# schematics.net
KiCad netlist of a schematic drawn in EasyEDA
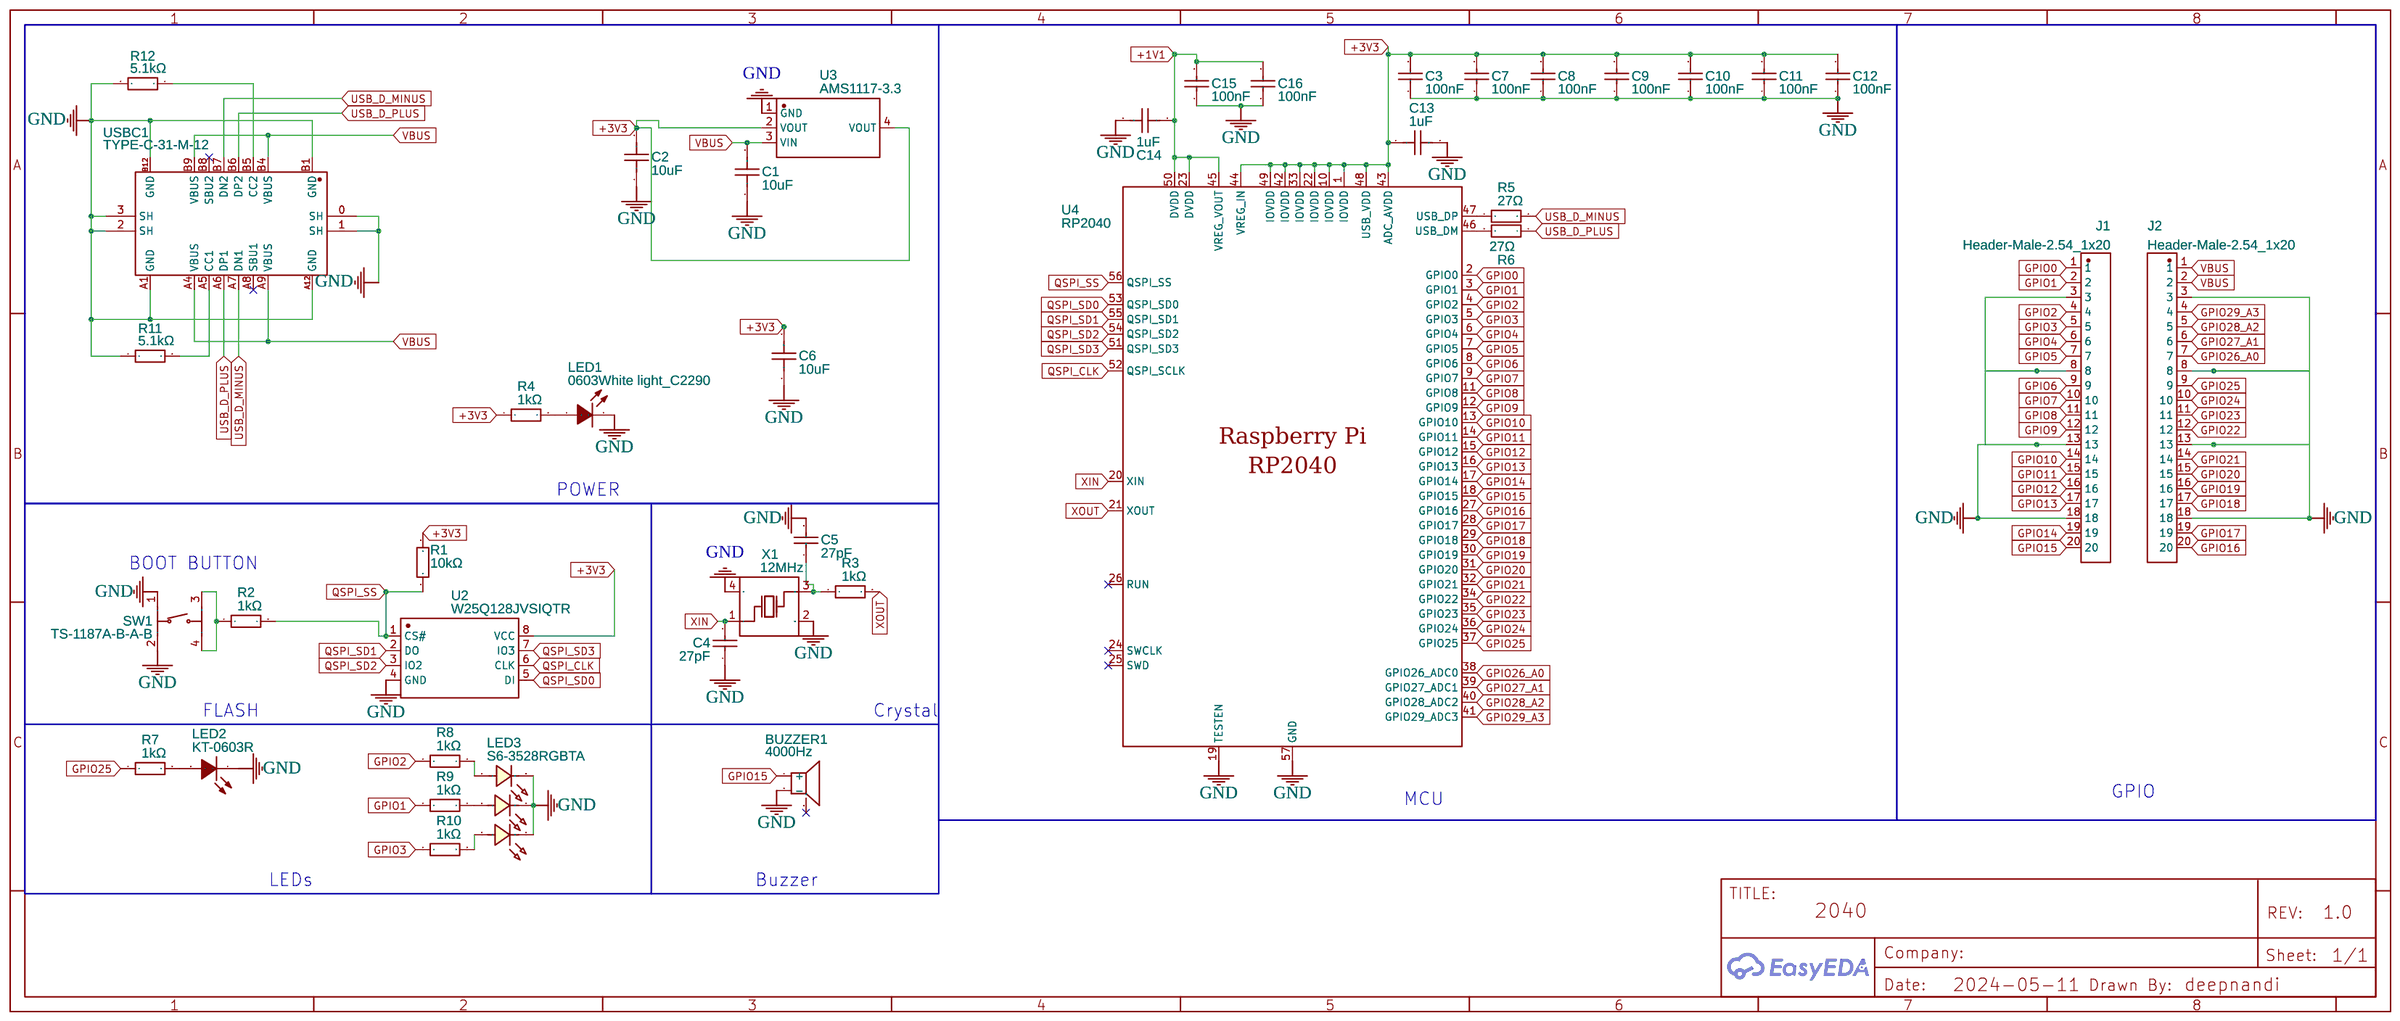
[diagram p0: schematic sheet]

(export (version "E")
  (design (tool "Eeschema 10.0.6"))
  (components
    (comp (ref "BUZZER1")
      (value "4000Hz")
      (fields (field (name "Manufacturer Part") "MLT-5020") (field (name "Manufacturer") "华能"))
      (libsource (lib "") (part "MLT-5020"))
    )
    (comp (ref "C1")
      (value "10uF")
      (fields
        (field (name "Manufacturer Part") "CL10A106KP8NNNC")
        (field (name "Manufacturer") "SAMSUNG(三星)")
      )
      (libsource (lib "") (part "CL10A106KP8NNNC"))
    )
    (comp (ref "C2")
      (value "10uF")
      (fields
        (field (name "Manufacturer Part") "CL10A106KP8NNNC")
        (field (name "Manufacturer") "SAMSUNG(三星)")
      )
      (libsource (lib "") (part "CL10A106KP8NNNC"))
    )
    (comp (ref "C3")
      (value "100nF")
      (fields
        (field (name "Manufacturer Part") "CL05B104KO5NNNC")
        (field (name "Manufacturer") "SAMSUNG(三星)")
      )
      (libsource (lib "") (part "CL05B104KO5NNNC"))
    )
    (comp (ref "C4")
      (value "27pF")
      (fields
        (field (name "Manufacturer Part") "CC0603JRNPO9BN270")
        (field (name "Manufacturer") "YAGEO(国巨)")
      )
      (libsource (lib "") (part "CC0603JRNPO9BN270_1"))
    )
    (comp (ref "C5")
      (value "27pF")
      (fields
        (field (name "Manufacturer Part") "CC0603JRNPO9BN270")
        (field (name "Manufacturer") "YAGEO(国巨)")
      )
      (libsource (lib "") (part "CC0603JRNPO9BN270"))
    )
    (comp (ref "C6")
      (value "10uF")
      (fields
        (field (name "Manufacturer Part") "CL10A106KP8NNNC")
        (field (name "Manufacturer") "SAMSUNG(三星)")
      )
      (libsource (lib "") (part "CL10A106KP8NNNC"))
    )
    (comp (ref "C7")
      (value "100nF")
      (fields
        (field (name "Manufacturer Part") "CL05B104KO5NNNC")
        (field (name "Manufacturer") "SAMSUNG(三星)")
      )
      (libsource (lib "") (part "CL05B104KO5NNNC"))
    )
    (comp (ref "C8")
      (value "100nF")
      (fields
        (field (name "Manufacturer Part") "CL05B104KO5NNNC")
        (field (name "Manufacturer") "SAMSUNG(三星)")
      )
      (libsource (lib "") (part "CL05B104KO5NNNC"))
    )
    (comp (ref "C9")
      (value "100nF")
      (fields
        (field (name "Manufacturer Part") "CL05B104KO5NNNC")
        (field (name "Manufacturer") "SAMSUNG(三星)")
      )
      (libsource (lib "") (part "CL05B104KO5NNNC"))
    )
    (comp (ref "C10")
      (value "100nF")
      (fields
        (field (name "Manufacturer Part") "CL05B104KO5NNNC")
        (field (name "Manufacturer") "SAMSUNG(三星)")
      )
      (libsource (lib "") (part "CL05B104KO5NNNC"))
    )
    (comp (ref "C11")
      (value "100nF")
      (fields
        (field (name "Manufacturer Part") "CL05B104KO5NNNC")
        (field (name "Manufacturer") "SAMSUNG(三星)")
      )
      (libsource (lib "") (part "CL05B104KO5NNNC"))
    )
    (comp (ref "C12")
      (value "100nF")
      (fields
        (field (name "Manufacturer Part") "CL05B104KO5NNNC")
        (field (name "Manufacturer") "SAMSUNG(三星)")
      )
      (libsource (lib "") (part "CL05B104KO5NNNC"))
    )
    (comp (ref "C13")
      (value "1uF")
      (fields
        (field (name "Manufacturer Part") "CL05A105KA5NQNC")
        (field (name "Manufacturer") "SAMSUNG(三星)")
      )
      (libsource (lib "") (part "CL05A105KA5NQNC"))
    )
    (comp (ref "C14")
      (value "1uF")
      (fields
        (field (name "Manufacturer Part") "CL05A105KA5NQNC")
        (field (name "Manufacturer") "SAMSUNG(三星)")
      )
      (libsource (lib "") (part "CL05A105KA5NQNC_1"))
    )
    (comp (ref "C15")
      (value "100nF")
      (fields
        (field (name "Manufacturer Part") "CL05B104KO5NNNC")
        (field (name "Manufacturer") "SAMSUNG(三星)")
      )
      (libsource (lib "") (part "CL05B104KO5NNNC"))
    )
    (comp (ref "C16")
      (value "100nF")
      (fields
        (field (name "Manufacturer Part") "CL05B104KO5NNNC")
        (field (name "Manufacturer") "SAMSUNG(三星)")
      )
      (libsource (lib "") (part "CL05B104KO5NNNC"))
    )
    (comp (ref "J1")
      (value "Header-Male-2.54_1x20")
      (fields (field (name "Manufacturer Part") "2.54-1*20P直针") (field (name "Manufacturer") "BOOMELE(博穆精密)"))
      (libsource (lib "") (part "Header-Male-2.54_1x20"))
    )
    (comp (ref "J2")
      (value "Header-Male-2.54_1x20")
      (fields (field (name "Manufacturer Part") "2.54-1*20P直针") (field (name "Manufacturer") "BOOMELE(博穆精密)"))
      (libsource (lib "") (part "Header-Male-2.54_1x20_1"))
    )
    (comp (ref "LED1")
      (value "0603White light_C2290")
      (fields (field (name "Manufacturer Part") "KT-0603白灯") (field (name "Manufacturer") "KENTO"))
      (libsource (lib "") (part "0603White light_C2290"))
    )
    (comp (ref "LED2")
      (value "KT-0603R")
      (fields (field (name "Manufacturer") "KENTO"))
      (libsource (lib "") (part "KT-0603R"))
    )
    (comp (ref "LED3")
      (value "S6-3528RGBTA")
      (fields (field (name "Manufacturer") "TUOZHAN(拓展光电)"))
      (libsource (lib "") (part "S6-3528RGBTA"))
    )
    (comp (ref "R1")
      (value "10kΩ")
      (fields
        (field (name "Manufacturer Part") "0402WGF1002TCE")
        (field (name "Manufacturer") "UNI-ROYAL(厚声)")
      )
      (libsource (lib "") (part "0402WGF1002TCE"))
    )
    (comp (ref "R2")
      (value "1kΩ")
      (fields
        (field (name "Manufacturer Part") "0402WGF1001TCE")
        (field (name "Manufacturer") "UNI-ROYAL(厚声)")
      )
      (libsource (lib "") (part "0402WGF1001TCE"))
    )
    (comp (ref "R3")
      (value "1kΩ")
      (fields
        (field (name "Manufacturer Part") "0402WGF1001TCE")
        (field (name "Manufacturer") "UNI-ROYAL(厚声)")
      )
      (libsource (lib "") (part "0402WGF1001TCE"))
    )
    (comp (ref "R4")
      (value "1kΩ")
      (fields
        (field (name "Manufacturer Part") "0402WGF1001TCE")
        (field (name "Manufacturer") "UNI-ROYAL(厚声)")
      )
      (libsource (lib "") (part "0402WGF1001TCE"))
    )
    (comp (ref "R5")
      (value "27Ω")
      (fields
        (field (name "Manufacturer Part") "0805W8F270JT5E")
        (field (name "Manufacturer") "UNI-ROYAL(厚声)")
      )
      (libsource (lib "") (part "0805W8F270JT5E_1"))
    )
    (comp (ref "R6")
      (value "27Ω")
      (fields
        (field (name "Manufacturer Part") "0805W8F270JT5E")
        (field (name "Manufacturer") "UNI-ROYAL(厚声)")
      )
      (libsource (lib "") (part "0805W8F270JT5E"))
    )
    (comp (ref "R7")
      (value "1kΩ")
      (fields
        (field (name "Manufacturer Part") "0402WGF1001TCE")
        (field (name "Manufacturer") "UNI-ROYAL(厚声)")
      )
      (libsource (lib "") (part "0402WGF1001TCE"))
    )
    (comp (ref "R8")
      (value "1kΩ")
      (fields
        (field (name "Manufacturer Part") "0402WGF1001TCE")
        (field (name "Manufacturer") "UNI-ROYAL(厚声)")
      )
      (libsource (lib "") (part "0402WGF1001TCE"))
    )
    (comp (ref "R9")
      (value "1kΩ")
      (fields
        (field (name "Manufacturer Part") "0402WGF1001TCE")
        (field (name "Manufacturer") "UNI-ROYAL(厚声)")
      )
      (libsource (lib "") (part "0402WGF1001TCE"))
    )
    (comp (ref "R10")
      (value "1kΩ")
      (fields
        (field (name "Manufacturer Part") "0402WGF1001TCE")
        (field (name "Manufacturer") "UNI-ROYAL(厚声)")
      )
      (libsource (lib "") (part "0402WGF1001TCE"))
    )
    (comp (ref "R11")
      (value "5.1kΩ")
      (fields (field (name "Manufacturer Part") "RTT02512JTH") (field (name "Manufacturer") "RALEC(旺诠)"))
      (libsource (lib "") (part "RTT02512JTH"))
    )
    (comp (ref "R12")
      (value "5.1kΩ")
      (fields (field (name "Manufacturer Part") "RTT02512JTH") (field (name "Manufacturer") "RALEC(旺诠)"))
      (libsource (lib "") (part "RTT02512JTH_1"))
    )
    (comp (ref "SW1")
      (value "TS-1187A-B-A-B")
      (fields (field (name "Manufacturer") "XKB Connectivity(中国星坤)"))
      (libsource (lib "") (part "TS-1187A-B-A-B"))
    )
    (comp (ref "U2")
      (value "W25Q128JVSIQTR")
      (fields (field (name "Manufacturer Part") "W25Q128JVSIQ") (field (name "Manufacturer") "WINBOND(华邦)"))
      (libsource (lib "") (part "W25Q128JVSIQTR"))
    )
    (comp (ref "U3")
      (value "AMS1117-3.3")
      (fields (field (name "Manufacturer") "AMS"))
      (libsource (lib "") (part "AMS1117-3.3"))
    )
    (comp (ref "U4")
      (value "RP2040")
      (fields (field (name "Manufacturer") "Raspberry Pi(树莓派)"))
      (libsource (lib "") (part "RP2040"))
    )
    (comp (ref "USBC1")
      (value "TYPE-C-31-M-12")
      (fields (field (name "Manufacturer") "韩国韩荣"))
      (libsource (lib "") (part "TYPE-C-31-M-12"))
    )
    (comp (ref "X1")
      (value "12MHz")
      (fields (field (name "Manufacturer Part") "X322512MSB4SI") (field (name "Manufacturer") "YXC(扬兴晶振)"))
      (libsource (lib "") (part "X322512MSB4SI"))
    )
  )
  (nets
    (net (code "1") (name "+1V1") (class "Default")
      (node (ref "C14") (pin "2") (pinfunction "2_2") (pintype "unspecified"))
      (node (ref "C15") (pin "2") (pinfunction "2_2") (pintype "input"))
      (node (ref "C16") (pin "2") (pinfunction "2_2") (pintype "input"))
      (node (ref "U4") (pin "23") (pinfunction "DVDD_23") (pintype "bidirectional"))
      (node (ref "U4") (pin "45") (pinfunction "VREG_VOUT_45") (pintype "bidirectional"))
      (node (ref "U4") (pin "50") (pinfunction "DVDD_50") (pintype "bidirectional"))
    )
    (net (code "2") (name "+3V3") (class "Default")
      (node (ref "C10") (pin "2") (pinfunction "2_2") (pintype "input"))
      (node (ref "C11") (pin "2") (pinfunction "2_2") (pintype "input"))
      (node (ref "C12") (pin "2") (pinfunction "2_2") (pintype "input"))
      (node (ref "C13") (pin "1") (pinfunction "1_1") (pintype "unspecified"))
      (node (ref "C2") (pin "2") (pinfunction "2_2") (pintype "unspecified"))
      (node (ref "C3") (pin "2") (pinfunction "2_2") (pintype "input"))
      (node (ref "C6") (pin "2") (pinfunction "2_2") (pintype "unspecified"))
      (node (ref "C7") (pin "2") (pinfunction "2_2") (pintype "input"))
      (node (ref "C8") (pin "2") (pinfunction "2_2") (pintype "input"))
      (node (ref "C9") (pin "2") (pinfunction "2_2") (pintype "input"))
      (node (ref "R1") (pin "2") (pinfunction "2_2") (pintype "input"))
      (node (ref "R4") (pin "1") (pinfunction "1_1") (pintype "input"))
      (node (ref "U2") (pin "8") (pinfunction "VCC_8") (pintype "unspecified"))
      (node (ref "U3") (pin "2") (pinfunction "VOUT_2") (pintype "unspecified"))
      (node (ref "U3") (pin "4") (pinfunction "VOUT_4") (pintype "unspecified"))
      (node (ref "U4") (pin "1") (pinfunction "IOVDD_1") (pintype "bidirectional"))
      (node (ref "U4") (pin "10") (pinfunction "IOVDD_10") (pintype "bidirectional"))
      (node (ref "U4") (pin "22") (pinfunction "IOVDD_22") (pintype "bidirectional"))
      (node (ref "U4") (pin "33") (pinfunction "IOVDD_33") (pintype "bidirectional"))
      (node (ref "U4") (pin "42") (pinfunction "IOVDD_42") (pintype "bidirectional"))
      (node (ref "U4") (pin "43") (pinfunction "ADC_AVDD_43") (pintype "bidirectional"))
      (node (ref "U4") (pin "44") (pinfunction "VREG_IN_44") (pintype "bidirectional"))
      (node (ref "U4") (pin "48") (pinfunction "USB_VDD_48") (pintype "bidirectional"))
      (node (ref "U4") (pin "49") (pinfunction "IOVDD_49") (pintype "bidirectional"))
    )
    (net (code "3") (name "GND") (class "Default")
      (node (ref "BUZZER1") (pin "2") (pinfunction "-_2") (pintype "unspecified"))
      (node (ref "C1") (pin "1") (pinfunction "1_1") (pintype "unspecified"))
      (node (ref "C10") (pin "1") (pinfunction "1_1") (pintype "input"))
      (node (ref "C11") (pin "1") (pinfunction "1_1") (pintype "input"))
      (node (ref "C12") (pin "1") (pinfunction "1_1") (pintype "input"))
      (node (ref "C13") (pin "2") (pinfunction "2_2") (pintype "unspecified"))
      (node (ref "C14") (pin "1") (pinfunction "1_1") (pintype "unspecified"))
      (node (ref "C15") (pin "1") (pinfunction "1_1") (pintype "input"))
      (node (ref "C16") (pin "1") (pinfunction "1_1") (pintype "input"))
      (node (ref "C2") (pin "1") (pinfunction "1_1") (pintype "unspecified"))
      (node (ref "C3") (pin "1") (pinfunction "1_1") (pintype "input"))
      (node (ref "C4") (pin "1") (pinfunction "1_1") (pintype "input"))
      (node (ref "C5") (pin "2") (pinfunction "2_2") (pintype "input"))
      (node (ref "C6") (pin "1") (pinfunction "1_1") (pintype "unspecified"))
      (node (ref "C7") (pin "1") (pinfunction "1_1") (pintype "input"))
      (node (ref "C8") (pin "1") (pinfunction "1_1") (pintype "input"))
      (node (ref "C9") (pin "1") (pinfunction "1_1") (pintype "input"))
      (node (ref "J1") (pin "13") (pinfunction "13_13") (pintype "unspecified"))
      (node (ref "J1") (pin "18") (pinfunction "18_18") (pintype "unspecified"))
      (node (ref "J1") (pin "3") (pinfunction "3_3") (pintype "unspecified"))
      (node (ref "J1") (pin "8") (pinfunction "8_8") (pintype "unspecified"))
      (node (ref "J2") (pin "13") (pinfunction "13_13") (pintype "unspecified"))
      (node (ref "J2") (pin "18") (pinfunction "18_18") (pintype "unspecified"))
      (node (ref "J2") (pin "3") (pinfunction "3_3") (pintype "unspecified"))
      (node (ref "J2") (pin "8") (pinfunction "8_8") (pintype "unspecified"))
      (node (ref "LED1") (pin "2") (pinfunction "K_2") (pintype "unspecified"))
      (node (ref "LED2") (pin "1") (pinfunction "K_1") (pintype "unspecified"))
      (node (ref "LED3") (pin "1") (pinfunction "1_1") (pintype "unspecified"))
      (node (ref "LED3") (pin "2") (pinfunction "2_2") (pintype "unspecified"))
      (node (ref "LED3") (pin "3") (pinfunction "3_3") (pintype "unspecified"))
      (node (ref "R11") (pin "1") (pinfunction "1_1") (pintype "input"))
      (node (ref "R12") (pin "2") (pinfunction "2_2") (pintype "input"))
      (node (ref "SW1") (pin "1") (pinfunction "A_1") (pintype "unspecified"))
      (node (ref "SW1") (pin "2") (pinfunction "B_2") (pintype "unspecified"))
      (node (ref "U2") (pin "4") (pinfunction "GND_4") (pintype "unspecified"))
      (node (ref "U3") (pin "1") (pinfunction "GND_1") (pintype "unspecified"))
      (node (ref "U4") (pin "19") (pinfunction "TESTEN_19") (pintype "unspecified"))
      (node (ref "U4") (pin "57") (pinfunction "GND_57") (pintype "bidirectional"))
      (node (ref "USBC1") (pin "0") (pinfunction "SH_0") (pintype "unspecified"))
      (node (ref "USBC1") (pin "1") (pinfunction "SH_1") (pintype "unspecified"))
      (node (ref "USBC1") (pin "2") (pinfunction "SH_2") (pintype "unspecified"))
      (node (ref "USBC1") (pin "3") (pinfunction "SH_3") (pintype "unspecified"))
      (node (ref "USBC1") (pin "A1") (pinfunction "GND_A1") (pintype "unspecified"))
      (node (ref "USBC1") (pin "A12") (pinfunction "GND_A12") (pintype "unspecified"))
      (node (ref "USBC1") (pin "B1") (pinfunction "GND_B1") (pintype "unspecified"))
      (node (ref "USBC1") (pin "B12") (pinfunction "GND_B12") (pintype "unspecified"))
      (node (ref "X1") (pin "2") (pinfunction "GND_2") (pintype "unspecified"))
      (node (ref "X1") (pin "4") (pinfunction "GND_4") (pintype "unspecified"))
    )
    (net (code "4") (name "GPIO0") (class "Default")
      (node (ref "J1") (pin "1") (pinfunction "1_1") (pintype "unspecified"))
      (node (ref "U4") (pin "2") (pinfunction "GPIO0_2") (pintype "bidirectional"))
    )
    (net (code "5") (name "GPIO1") (class "Default")
      (node (ref "J1") (pin "2") (pinfunction "2_2") (pintype "unspecified"))
      (node (ref "R9") (pin "1") (pinfunction "1_1") (pintype "input"))
      (node (ref "U4") (pin "3") (pinfunction "GPIO1_3") (pintype "bidirectional"))
    )
    (net (code "6") (name "GPIO2") (class "Default")
      (node (ref "J1") (pin "4") (pinfunction "4_4") (pintype "unspecified"))
      (node (ref "R8") (pin "1") (pinfunction "1_1") (pintype "input"))
      (node (ref "U4") (pin "4") (pinfunction "GPIO2_4") (pintype "bidirectional"))
    )
    (net (code "7") (name "GPIO3") (class "Default")
      (node (ref "J1") (pin "5") (pinfunction "5_5") (pintype "unspecified"))
      (node (ref "R10") (pin "1") (pinfunction "1_1") (pintype "input"))
      (node (ref "U4") (pin "5") (pinfunction "GPIO3_5") (pintype "bidirectional"))
    )
    (net (code "8") (name "GPIO4") (class "Default")
      (node (ref "J1") (pin "6") (pinfunction "6_6") (pintype "unspecified"))
      (node (ref "U4") (pin "6") (pinfunction "GPIO4_6") (pintype "bidirectional"))
    )
    (net (code "9") (name "GPIO5") (class "Default")
      (node (ref "J1") (pin "7") (pinfunction "7_7") (pintype "unspecified"))
      (node (ref "U4") (pin "7") (pinfunction "GPIO5_7") (pintype "bidirectional"))
    )
    (net (code "10") (name "GPIO6") (class "Default")
      (node (ref "J1") (pin "9") (pinfunction "9_9") (pintype "unspecified"))
      (node (ref "U4") (pin "8") (pinfunction "GPIO6_8") (pintype "bidirectional"))
    )
    (net (code "11") (name "GPIO7") (class "Default")
      (node (ref "J1") (pin "10") (pinfunction "10_10") (pintype "unspecified"))
      (node (ref "U4") (pin "9") (pinfunction "GPIO7_9") (pintype "bidirectional"))
    )
    (net (code "12") (name "GPIO8") (class "Default")
      (node (ref "J1") (pin "11") (pinfunction "11_11") (pintype "unspecified"))
      (node (ref "U4") (pin "11") (pinfunction "GPIO8_11") (pintype "bidirectional"))
    )
    (net (code "13") (name "GPIO9") (class "Default")
      (node (ref "J1") (pin "12") (pinfunction "12_12") (pintype "unspecified"))
      (node (ref "U4") (pin "12") (pinfunction "GPIO9_12") (pintype "bidirectional"))
    )
    (net (code "14") (name "GPIO10") (class "Default")
      (node (ref "J1") (pin "14") (pinfunction "14_14") (pintype "unspecified"))
      (node (ref "U4") (pin "13") (pinfunction "GPIO10_13") (pintype "bidirectional"))
    )
    (net (code "15") (name "GPIO11") (class "Default")
      (node (ref "J1") (pin "15") (pinfunction "15_15") (pintype "unspecified"))
      (node (ref "U4") (pin "14") (pinfunction "GPIO11_14") (pintype "bidirectional"))
    )
    (net (code "16") (name "GPIO12") (class "Default")
      (node (ref "J1") (pin "16") (pinfunction "16_16") (pintype "unspecified"))
      (node (ref "U4") (pin "15") (pinfunction "GPIO12_15") (pintype "bidirectional"))
    )
    (net (code "17") (name "GPIO13") (class "Default")
      (node (ref "J1") (pin "17") (pinfunction "17_17") (pintype "unspecified"))
      (node (ref "U4") (pin "16") (pinfunction "GPIO13_16") (pintype "bidirectional"))
    )
    (net (code "18") (name "GPIO14") (class "Default")
      (node (ref "J1") (pin "19") (pinfunction "19_19") (pintype "unspecified"))
      (node (ref "U4") (pin "17") (pinfunction "GPIO14_17") (pintype "bidirectional"))
    )
    (net (code "19") (name "GPIO15") (class "Default")
      (node (ref "BUZZER1") (pin "1") (pinfunction "+_1") (pintype "unspecified"))
      (node (ref "J1") (pin "20") (pinfunction "20_20") (pintype "unspecified"))
      (node (ref "U4") (pin "18") (pinfunction "GPIO15_18") (pintype "bidirectional"))
    )
    (net (code "20") (name "GPIO16") (class "Default")
      (node (ref "J2") (pin "20") (pinfunction "20_20") (pintype "unspecified"))
      (node (ref "U4") (pin "27") (pinfunction "GPIO16_27") (pintype "bidirectional"))
    )
    (net (code "21") (name "GPIO17") (class "Default")
      (node (ref "J2") (pin "19") (pinfunction "19_19") (pintype "unspecified"))
      (node (ref "U4") (pin "28") (pinfunction "GPIO17_28") (pintype "bidirectional"))
    )
    (net (code "22") (name "GPIO18") (class "Default")
      (node (ref "J2") (pin "17") (pinfunction "17_17") (pintype "unspecified"))
      (node (ref "U4") (pin "29") (pinfunction "GPIO18_29") (pintype "bidirectional"))
    )
    (net (code "23") (name "GPIO19") (class "Default")
      (node (ref "J2") (pin "16") (pinfunction "16_16") (pintype "unspecified"))
      (node (ref "U4") (pin "30") (pinfunction "GPIO19_30") (pintype "bidirectional"))
    )
    (net (code "24") (name "GPIO20") (class "Default")
      (node (ref "J2") (pin "15") (pinfunction "15_15") (pintype "unspecified"))
      (node (ref "U4") (pin "31") (pinfunction "GPIO20_31") (pintype "bidirectional"))
    )
    (net (code "25") (name "GPIO21") (class "Default")
      (node (ref "J2") (pin "14") (pinfunction "14_14") (pintype "unspecified"))
      (node (ref "U4") (pin "32") (pinfunction "GPIO21_32") (pintype "bidirectional"))
    )
    (net (code "26") (name "GPIO22") (class "Default")
      (node (ref "J2") (pin "12") (pinfunction "12_12") (pintype "unspecified"))
      (node (ref "U4") (pin "34") (pinfunction "GPIO22_34") (pintype "bidirectional"))
    )
    (net (code "27") (name "GPIO23") (class "Default")
      (node (ref "J2") (pin "11") (pinfunction "11_11") (pintype "unspecified"))
      (node (ref "U4") (pin "35") (pinfunction "GPIO23_35") (pintype "bidirectional"))
    )
    (net (code "28") (name "GPIO24") (class "Default")
      (node (ref "J2") (pin "10") (pinfunction "10_10") (pintype "unspecified"))
      (node (ref "U4") (pin "36") (pinfunction "GPIO24_36") (pintype "bidirectional"))
    )
    (net (code "29") (name "GPIO25") (class "Default")
      (node (ref "J2") (pin "9") (pinfunction "9_9") (pintype "unspecified"))
      (node (ref "R7") (pin "1") (pinfunction "1_1") (pintype "input"))
      (node (ref "U4") (pin "37") (pinfunction "GPIO25_37") (pintype "bidirectional"))
    )
    (net (code "30") (name "GPIO26_A0") (class "Default")
      (node (ref "J2") (pin "7") (pinfunction "7_7") (pintype "unspecified"))
      (node (ref "U4") (pin "38") (pinfunction "GPIO26_ADC0_38") (pintype "bidirectional"))
    )
    (net (code "31") (name "GPIO27_A1") (class "Default")
      (node (ref "J2") (pin "6") (pinfunction "6_6") (pintype "unspecified"))
      (node (ref "U4") (pin "39") (pinfunction "GPIO27_ADC1_39") (pintype "bidirectional"))
    )
    (net (code "32") (name "GPIO28_A2") (class "Default")
      (node (ref "J2") (pin "5") (pinfunction "5_5") (pintype "unspecified"))
      (node (ref "U4") (pin "40") (pinfunction "GPIO28_ADC2_40") (pintype "bidirectional"))
    )
    (net (code "33") (name "GPIO29_A3") (class "Default")
      (node (ref "J2") (pin "4") (pinfunction "4_4") (pintype "unspecified"))
      (node (ref "U4") (pin "41") (pinfunction "GPIO29_ADC3_41") (pintype "bidirectional"))
    )
    (net (code "34") (name "Net-(LED1-A)") (class "Default")
      (node (ref "LED1") (pin "1") (pinfunction "A_1") (pintype "unspecified"))
      (node (ref "R4") (pin "2") (pinfunction "2_2") (pintype "input"))
    )
    (net (code "35") (name "Net-(LED2-A)") (class "Default")
      (node (ref "LED2") (pin "2") (pinfunction "A_2") (pintype "unspecified"))
      (node (ref "R7") (pin "2") (pinfunction "2_2") (pintype "input"))
    )
    (net (code "36") (name "Net-(LED3-Pad4)") (class "Default")
      (node (ref "LED3") (pin "4") (pinfunction "4_4") (pintype "unspecified"))
      (node (ref "R8") (pin "2") (pinfunction "2_2") (pintype "input"))
    )
    (net (code "37") (name "Net-(LED3-Pad5)") (class "Default")
      (node (ref "LED3") (pin "5") (pinfunction "5_5") (pintype "unspecified"))
      (node (ref "R9") (pin "2") (pinfunction "2_2") (pintype "input"))
    )
    (net (code "38") (name "Net-(LED3-Pad6)") (class "Default")
      (node (ref "LED3") (pin "6") (pinfunction "6_6") (pintype "unspecified"))
      (node (ref "R10") (pin "2") (pinfunction "2_2") (pintype "input"))
    )
    (net (code "39") (name "Net-(SW1-C)") (class "Default")
      (node (ref "R2") (pin "1") (pinfunction "1_1") (pintype "input"))
      (node (ref "SW1") (pin "3") (pinfunction "C_3") (pintype "unspecified"))
      (node (ref "SW1") (pin "4") (pinfunction "D_4") (pintype "unspecified"))
    )
    (net (code "40") (name "Net-(U4-USB_DM)") (class "Default")
      (node (ref "R6") (pin "2") (pinfunction "2_2") (pintype "input"))
      (node (ref "U4") (pin "46") (pinfunction "USB_DM_46") (pintype "bidirectional"))
    )
    (net (code "41") (name "Net-(U4-USB_DP)") (class "Default")
      (node (ref "R5") (pin "1") (pinfunction "1_1") (pintype "input"))
      (node (ref "U4") (pin "47") (pinfunction "USB_DP_47") (pintype "bidirectional"))
    )
    (net (code "42") (name "Net-(USBC1-CC1)") (class "Default")
      (node (ref "R11") (pin "2") (pinfunction "2_2") (pintype "input"))
      (node (ref "USBC1") (pin "A5") (pinfunction "CC1_A5") (pintype "unspecified"))
    )
    (net (code "43") (name "Net-(USBC1-CC2)") (class "Default")
      (node (ref "R12") (pin "1") (pinfunction "1_1") (pintype "input"))
      (node (ref "USBC1") (pin "B5") (pinfunction "CC2_B5") (pintype "unspecified"))
    )
    (net (code "44") (name "Net-(X1-OSC2)") (class "Default")
      (node (ref "C5") (pin "1") (pinfunction "1_1") (pintype "input"))
      (node (ref "R3") (pin "1") (pinfunction "1_1") (pintype "input"))
      (node (ref "X1") (pin "3") (pinfunction "OSC2_3") (pintype "unspecified"))
    )
    (net (code "45") (name "QSPI_CLK") (class "Default")
      (node (ref "U2") (pin "6") (pinfunction "CLK_6") (pintype "unspecified"))
      (node (ref "U4") (pin "52") (pinfunction "QSPI_SCLK_52") (pintype "output"))
    )
    (net (code "46") (name "QSPI_SD0") (class "Default")
      (node (ref "U2") (pin "5") (pinfunction "DI_5") (pintype "unspecified"))
      (node (ref "U4") (pin "53") (pinfunction "QSPI_SD0_53") (pintype "bidirectional"))
    )
    (net (code "47") (name "QSPI_SD1") (class "Default")
      (node (ref "U2") (pin "2") (pinfunction "DO_2") (pintype "unspecified"))
      (node (ref "U4") (pin "55") (pinfunction "QSPI_SD1_55") (pintype "bidirectional"))
    )
    (net (code "48") (name "QSPI_SD2") (class "Default")
      (node (ref "U2") (pin "3") (pinfunction "IO2_3") (pintype "unspecified"))
      (node (ref "U4") (pin "54") (pinfunction "QSPI_SD2_54") (pintype "bidirectional"))
    )
    (net (code "49") (name "QSPI_SD3") (class "Default")
      (node (ref "U2") (pin "7") (pinfunction "IO3_7") (pintype "unspecified"))
      (node (ref "U4") (pin "51") (pinfunction "QSPI_SD3_51") (pintype "bidirectional"))
    )
    (net (code "50") (name "QSPI_SS") (class "Default")
      (node (ref "R1") (pin "1") (pinfunction "1_1") (pintype "input"))
      (node (ref "R2") (pin "2") (pinfunction "2_2") (pintype "input"))
      (node (ref "U2") (pin "1") (pinfunction "CS#_1") (pintype "unspecified"))
      (node (ref "U4") (pin "56") (pinfunction "QSPI_SS_56") (pintype "bidirectional"))
    )
    (net (code "51") (name "USB_D_MINUS") (class "Default")
      (node (ref "R5") (pin "2") (pinfunction "2_2") (pintype "input"))
      (node (ref "USBC1") (pin "A7") (pinfunction "DN1_A7") (pintype "unspecified"))
      (node (ref "USBC1") (pin "B7") (pinfunction "DN2_B7") (pintype "unspecified"))
    )
    (net (code "52") (name "USB_D_PLUS") (class "Default")
      (node (ref "R6") (pin "1") (pinfunction "1_1") (pintype "input"))
      (node (ref "USBC1") (pin "A6") (pinfunction "DP1_A6") (pintype "unspecified"))
      (node (ref "USBC1") (pin "B6") (pinfunction "DP2_B6") (pintype "unspecified"))
    )
    (net (code "53") (name "VBUS") (class "Default")
      (node (ref "C1") (pin "2") (pinfunction "2_2") (pintype "unspecified"))
      (node (ref "J2") (pin "1") (pinfunction "1_1") (pintype "unspecified"))
      (node (ref "J2") (pin "2") (pinfunction "2_2") (pintype "unspecified"))
      (node (ref "U3") (pin "3") (pinfunction "VIN_3") (pintype "unspecified"))
      (node (ref "USBC1") (pin "A4") (pinfunction "VBUS_A4") (pintype "unspecified"))
      (node (ref "USBC1") (pin "A9") (pinfunction "VBUS_A9") (pintype "unspecified"))
      (node (ref "USBC1") (pin "B4") (pinfunction "VBUS_B4") (pintype "unspecified"))
      (node (ref "USBC1") (pin "B9") (pinfunction "VBUS_B9") (pintype "unspecified"))
    )
    (net (code "54") (name "XIN") (class "Default")
      (node (ref "C4") (pin "2") (pinfunction "2_2") (pintype "input"))
      (node (ref "U4") (pin "20") (pinfunction "XIN_20") (pintype "input"))
      (node (ref "X1") (pin "1") (pinfunction "OSC1_1") (pintype "unspecified"))
    )
    (net (code "55") (name "XOUT") (class "Default")
      (node (ref "R3") (pin "2") (pinfunction "2_2") (pintype "input"))
      (node (ref "U4") (pin "21") (pinfunction "XOUT_21") (pintype "unspecified"))
    )
    (net (code "56") (name "unconnected-(BUZZER1-NC-Pad3)") (class "Default")
      (node (ref "BUZZER1") (pin "3") (pinfunction "NC_3") (pintype "unspecified+no_connect"))
    )
    (net (code "57") (name "unconnected-(U4-RUN-Pad26)") (class "Default")
      (node (ref "U4") (pin "26") (pinfunction "RUN_26") (pintype "input+no_connect"))
    )
    (net (code "58") (name "unconnected-(U4-SWCLK-Pad24)") (class "Default")
      (node (ref "U4") (pin "24") (pinfunction "SWCLK_24") (pintype "output+no_connect"))
    )
    (net (code "59") (name "unconnected-(U4-SWD-Pad25)") (class "Default")
      (node (ref "U4") (pin "25") (pinfunction "SWD_25") (pintype "bidirectional+no_connect"))
    )
    (net (code "60") (name "unconnected-(USBC1-SBU1-PadA8)") (class "Default")
      (node (ref "USBC1") (pin "A8") (pinfunction "SBU1_A8") (pintype "unspecified+no_connect"))
    )
    (net (code "61") (name "unconnected-(USBC1-SBU2-PadB8)") (class "Default")
      (node (ref "USBC1") (pin "B8") (pinfunction "SBU2_B8") (pintype "unspecified+no_connect"))
    )
  )
)
